# S12_Clocks.net
KiCad netlist of a schematic drawn in Altium Designer
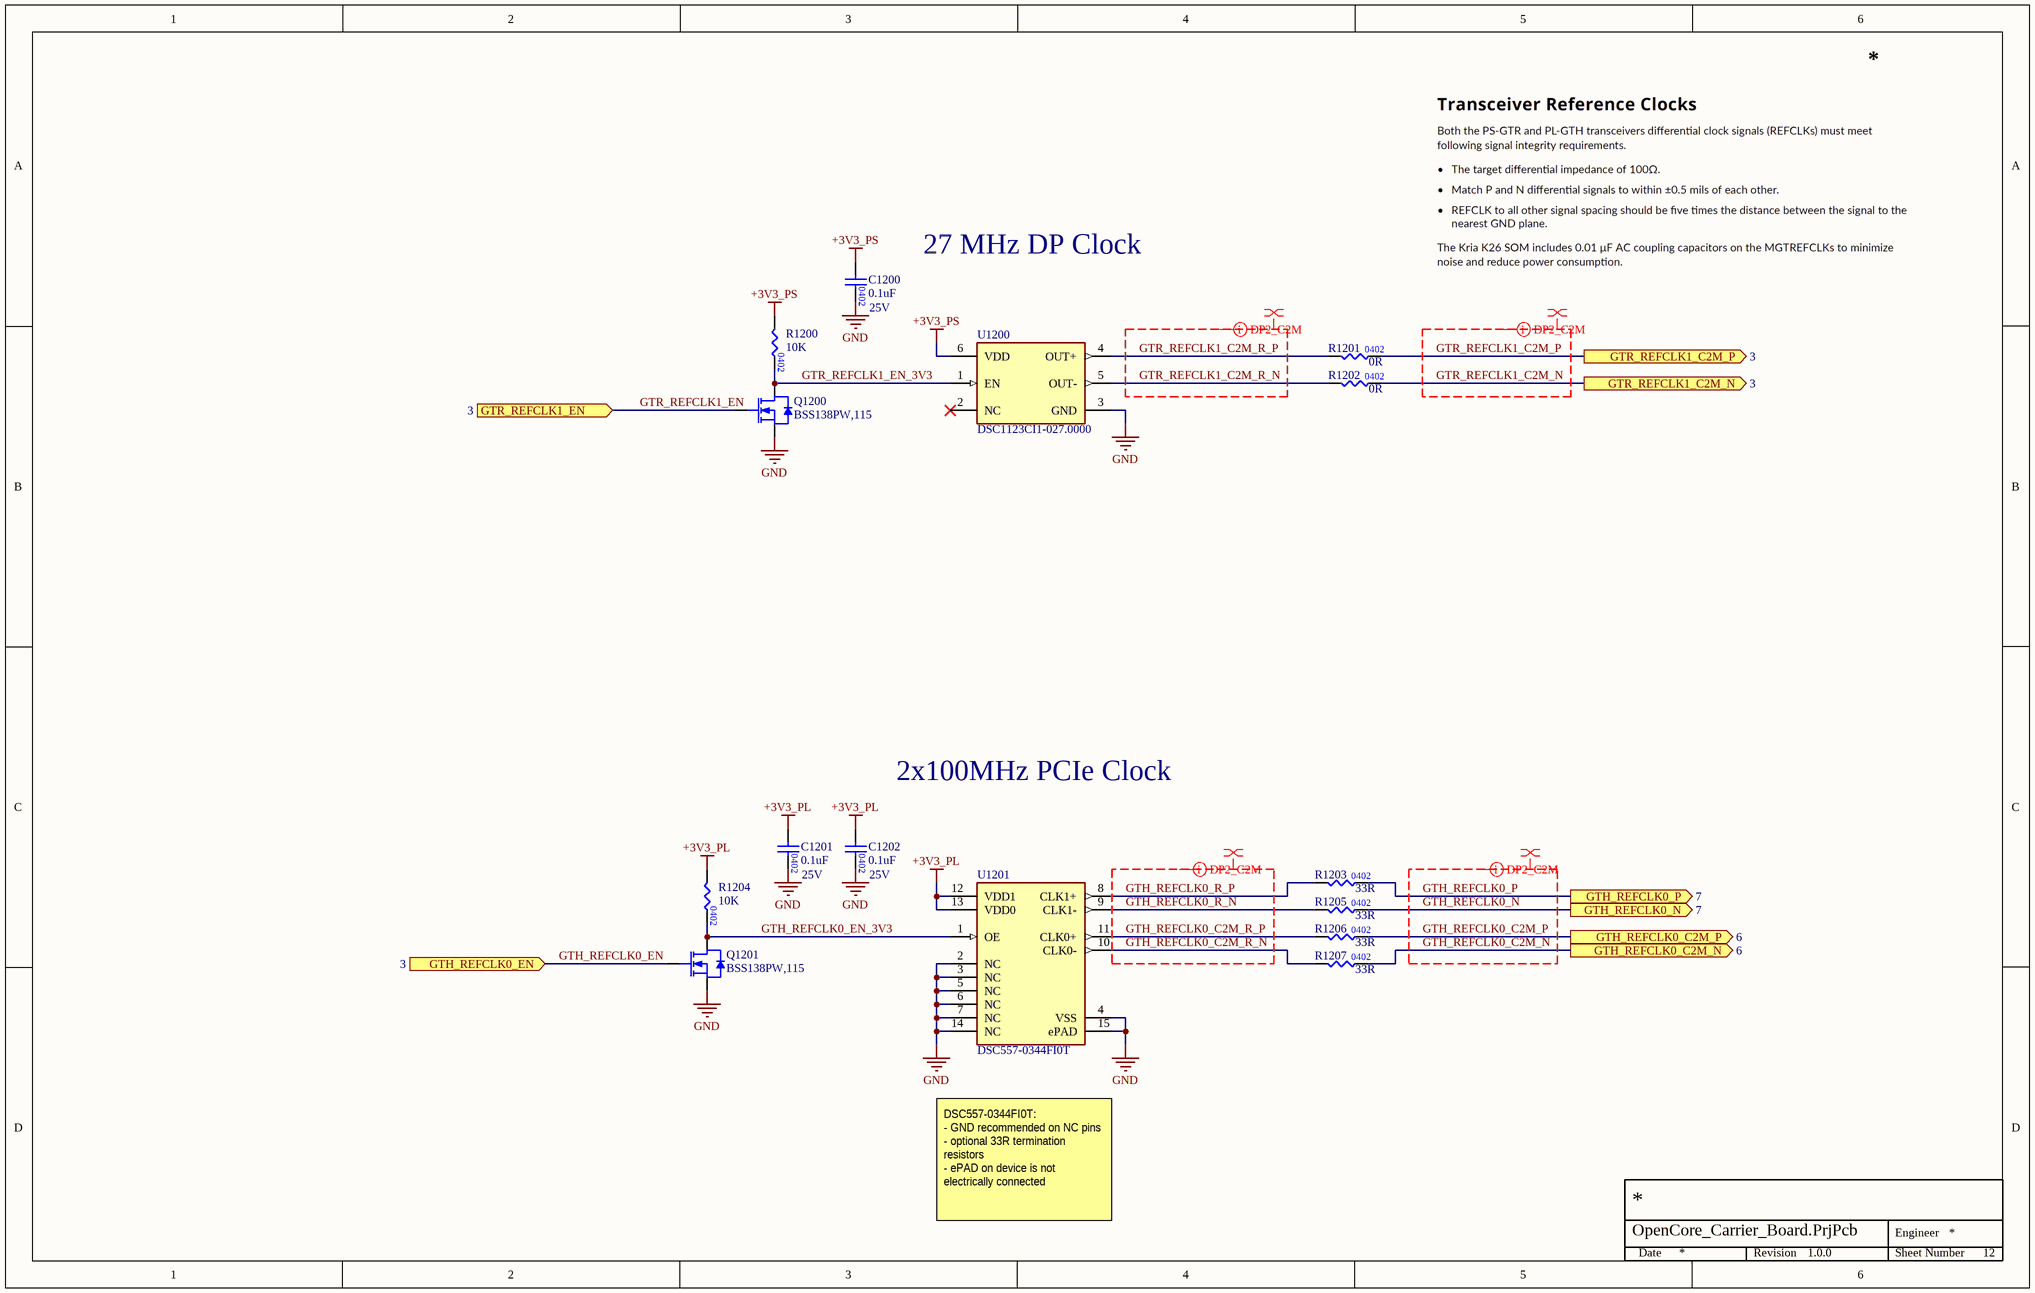
[diagram p0: S12_Clocks.SchDoc]

(export (version "E")
  (design (tool "Eeschema 10.0.6"))
  (components
    (comp (ref "C1200")
      (value "0.1uF")
      (footprint "CAP0402")
      (description "CAP CER 0.1UF 25V X5R 0402")
      (fields
        (field (name "MANUFACTURER") "Samsung Electro-Mechanics")
        (field (name "TOLERANCE") "10%")
        (field (name "VOLTAGE RATING") "25V")
      )
      (libsource (lib "OpenCore_Sch_Lib") (part "CAP_CL05A104KA5NNNC"))
    )
    (comp (ref "C1201")
      (value "0.1uF")
      (footprint "CAP0402")
      (description "CAP CER 0.1UF 25V X5R 0402")
      (fields
        (field (name "MANUFACTURER") "Samsung Electro-Mechanics")
        (field (name "TOLERANCE") "10%")
        (field (name "VOLTAGE RATING") "25V")
      )
      (libsource (lib "OpenCore_Sch_Lib") (part "CAP_CL05A104KA5NNNC"))
    )
    (comp (ref "C1202")
      (value "0.1uF")
      (footprint "CAP0402")
      (description "CAP CER 0.1UF 25V X5R 0402")
      (fields
        (field (name "MANUFACTURER") "Samsung Electro-Mechanics")
        (field (name "TOLERANCE") "10%")
        (field (name "VOLTAGE RATING") "25V")
      )
      (libsource (lib "OpenCore_Sch_Lib") (part "CAP_CL05A104KA5NNNC"))
    )
    (comp (ref "Q1200")
      (value "BSS138PW,115")
      (footprint "NEXPERIA_SOT323")
      (description "MOSFET N-CH 60V 320MA SOT323")
      (libsource (lib "OpenCore_Sch_Lib") (part "BSS138PW,115"))
    )
    (comp (ref "Q1201")
      (value "BSS138PW,115")
      (footprint "NEXPERIA_SOT323")
      (description "MOSFET N-CH 60V 320MA SOT323")
      (libsource (lib "OpenCore_Sch_Lib") (part "BSS138PW,115"))
    )
    (comp (ref "R1200")
      (value "RES_0402")
      (footprint "RES0402")
      (description "RES 10K OHM 1% 1/16W 0402")
      (fields
        (field (name "MANUFACTURER") "YAGEO")
        (field (name "MANUFACTURER PART NUMBER") "RC0402FR-0710KL")
        (field (name "RESISTANCE") "10K")
      )
      (libsource (lib "OpenCore_Sch_Lib") (part ".RES_RC0402FR-0710KL"))
    )
    (comp (ref "R1201")
      (value "RES_0402")
      (footprint "RES0402")
      (description "RES 0 OHM JUMPER 1/16W 0402")
      (fields
        (field (name "MANUFACTURER") "YAGEO")
        (field (name "MANUFACTURER PART NUMBER") "RC0402JR-070RL")
        (field (name "RESISTANCE") "0R")
      )
      (libsource (lib "OpenCore_Sch_Lib") (part ".RES_RC0402JR-070RL"))
    )
    (comp (ref "R1202")
      (value "RES_0402")
      (footprint "RES0402")
      (description "RES 0 OHM JUMPER 1/16W 0402")
      (fields
        (field (name "MANUFACTURER") "YAGEO")
        (field (name "MANUFACTURER PART NUMBER") "RC0402JR-070RL")
        (field (name "RESISTANCE") "0R")
      )
      (libsource (lib "OpenCore_Sch_Lib") (part ".RES_RC0402JR-070RL"))
    )
    (comp (ref "R1203")
      (value "RES_0402")
      (footprint "RES0402")
      (description "RES 33 OHM 1% 1/16W 0402")
      (fields
        (field (name "MANUFACTURER") "YAGEO")
        (field (name "MANUFACTURER PART NUMBER") "RC0402FR-0733RL")
        (field (name "RESISTANCE") "33R")
      )
      (libsource (lib "OpenCore_Sch_Lib") (part ".RES_RC0402FR-0733RL"))
    )
    (comp (ref "R1204")
      (value "RES_0402")
      (footprint "RES0402")
      (description "RES 10K OHM 1% 1/16W 0402")
      (fields
        (field (name "MANUFACTURER") "YAGEO")
        (field (name "MANUFACTURER PART NUMBER") "RC0402FR-0710KL")
        (field (name "RESISTANCE") "10K")
      )
      (libsource (lib "OpenCore_Sch_Lib") (part ".RES_RC0402FR-0710KL"))
    )
    (comp (ref "R1205")
      (value "RES_0402")
      (footprint "RES0402")
      (description "RES 33 OHM 1% 1/16W 0402")
      (fields
        (field (name "MANUFACTURER") "YAGEO")
        (field (name "MANUFACTURER PART NUMBER") "RC0402FR-0733RL")
        (field (name "RESISTANCE") "33R")
      )
      (libsource (lib "OpenCore_Sch_Lib") (part ".RES_RC0402FR-0733RL"))
    )
    (comp (ref "R1206")
      (value "RES_0402")
      (footprint "RES0402")
      (description "RES 33 OHM 1% 1/16W 0402")
      (fields
        (field (name "MANUFACTURER") "YAGEO")
        (field (name "MANUFACTURER PART NUMBER") "RC0402FR-0733RL")
        (field (name "RESISTANCE") "33R")
      )
      (libsource (lib "OpenCore_Sch_Lib") (part ".RES_RC0402FR-0733RL"))
    )
    (comp (ref "R1207")
      (value "RES_0402")
      (footprint "RES0402")
      (description "RES 33 OHM 1% 1/16W 0402")
      (fields
        (field (name "MANUFACTURER") "YAGEO")
        (field (name "MANUFACTURER PART NUMBER") "RC0402FR-0733RL")
        (field (name "RESISTANCE") "33R")
      )
      (libsource (lib "OpenCore_Sch_Lib") (part ".RES_RC0402FR-0733RL"))
    )
    (comp (ref "U1200")
      (value "DSC1123CI1-027.0000")
      (footprint "MICROCHIP_VDFN-6_H5A")
      (description "MEMS OSC XO 27.0000MHZ LVDS SMD")
      (libsource (lib "OpenCore_Sch_Lib") (part "DSC1123CI1-027.0000"))
    )
    (comp (ref "U1201")
      (value "DSC557-0344FI0T")
      (footprint "MICROCHIP_QFN2532-14")
      (description "IC CLOCK GEN PCIE 14QFN")
      (libsource (lib "OpenCore_Sch_Lib") (part "DSC557-0344FI0T"))
    )
  )
  (nets
    (net (code "1") (name "+3V3_PL") (class "Default")
      (node (ref "C1201") (pin "1") (pinfunction "1_1") (pintype "passive"))
      (node (ref "C1202") (pin "1") (pinfunction "1_1") (pintype "passive"))
      (node (ref "R1204") (pin "1") (pinfunction "1_1") (pintype "passive"))
      (node (ref "U1201") (pin "12") (pinfunction "VDD1_12") (pintype "power_in"))
      (node (ref "U1201") (pin "13") (pinfunction "VDD0_13") (pintype "power_in"))
    )
    (net (code "2") (name "+3V3_PS") (class "Default")
      (node (ref "C1200") (pin "1") (pinfunction "1_1") (pintype "passive"))
      (node (ref "R1200") (pin "1") (pinfunction "1_1") (pintype "passive"))
      (node (ref "U1200") (pin "6") (pinfunction "VDD_6") (pintype "power_in"))
    )
    (net (code "3") (name "/GTH_REFCLK0_C2M_N") (class "Default")
      (node (ref "R1207") (pin "2") (pinfunction "2_2") (pintype "passive"))
    )
    (net (code "4") (name "/GTH_REFCLK0_C2M_P") (class "Default")
      (node (ref "R1206") (pin "2") (pinfunction "2_2") (pintype "passive"))
    )
    (net (code "5") (name "/GTH_REFCLK0_C2M_R_N") (class "Default")
      (node (ref "R1207") (pin "1") (pinfunction "1_1") (pintype "passive"))
      (node (ref "U1201") (pin "10") (pinfunction "CLK0-_10") (pintype "output"))
    )
    (net (code "6") (name "/GTH_REFCLK0_C2M_R_P") (class "Default")
      (node (ref "R1206") (pin "1") (pinfunction "1_1") (pintype "passive"))
      (node (ref "U1201") (pin "11") (pinfunction "CLK0+_11") (pintype "output"))
    )
    (net (code "7") (name "/GTH_REFCLK0_EN") (class "Default")
      (node (ref "Q1201") (pin "1") (pinfunction "Gate_1") (pintype "passive"))
    )
    (net (code "8") (name "/GTH_REFCLK0_EN_3V3") (class "Default")
      (node (ref "Q1201") (pin "3") (pinfunction "Drain_3") (pintype "passive"))
      (node (ref "R1204") (pin "2") (pinfunction "2_2") (pintype "passive"))
      (node (ref "U1201") (pin "1") (pinfunction "OE_1") (pintype "input"))
    )
    (net (code "9") (name "/GTH_REFCLK0_N") (class "Default")
      (node (ref "R1205") (pin "2") (pinfunction "2_2") (pintype "passive"))
    )
    (net (code "10") (name "/GTH_REFCLK0_P") (class "Default")
      (node (ref "R1203") (pin "2") (pinfunction "2_2") (pintype "passive"))
    )
    (net (code "11") (name "/GTH_REFCLK0_R_N") (class "Default")
      (node (ref "R1205") (pin "1") (pinfunction "1_1") (pintype "passive"))
      (node (ref "U1201") (pin "9") (pinfunction "CLK1-_9") (pintype "output"))
    )
    (net (code "12") (name "/GTH_REFCLK0_R_P") (class "Default")
      (node (ref "R1203") (pin "1") (pinfunction "1_1") (pintype "passive"))
      (node (ref "U1201") (pin "8") (pinfunction "CLK1+_8") (pintype "output"))
    )
    (net (code "13") (name "/GTR_REFCLK1_C2M_N") (class "Default")
      (node (ref "R1202") (pin "2") (pinfunction "2_2") (pintype "passive"))
    )
    (net (code "14") (name "/GTR_REFCLK1_C2M_P") (class "Default")
      (node (ref "R1201") (pin "2") (pinfunction "2_2") (pintype "passive"))
    )
    (net (code "15") (name "/GTR_REFCLK1_C2M_R_N") (class "Default")
      (node (ref "R1202") (pin "1") (pinfunction "1_1") (pintype "passive"))
      (node (ref "U1200") (pin "5") (pinfunction "OUT-_5") (pintype "output"))
    )
    (net (code "16") (name "/GTR_REFCLK1_C2M_R_P") (class "Default")
      (node (ref "R1201") (pin "1") (pinfunction "1_1") (pintype "passive"))
      (node (ref "U1200") (pin "4") (pinfunction "OUT+_4") (pintype "output"))
    )
    (net (code "17") (name "/GTR_REFCLK1_EN") (class "Default")
      (node (ref "Q1200") (pin "1") (pinfunction "Gate_1") (pintype "passive"))
    )
    (net (code "18") (name "/GTR_REFCLK1_EN_3V3") (class "Default")
      (node (ref "Q1200") (pin "3") (pinfunction "Drain_3") (pintype "passive"))
      (node (ref "R1200") (pin "2") (pinfunction "2_2") (pintype "passive"))
      (node (ref "U1200") (pin "1") (pinfunction "EN_1") (pintype "input"))
    )
    (net (code "19") (name "GND") (class "Default")
      (node (ref "C1200") (pin "2") (pinfunction "2_2") (pintype "passive"))
      (node (ref "C1201") (pin "2") (pinfunction "2_2") (pintype "passive"))
      (node (ref "C1202") (pin "2") (pinfunction "2_2") (pintype "passive"))
      (node (ref "Q1200") (pin "2") (pinfunction "Source_2") (pintype "passive"))
      (node (ref "Q1201") (pin "2") (pinfunction "Source_2") (pintype "passive"))
      (node (ref "U1200") (pin "3") (pinfunction "GND_3") (pintype "power_in"))
      (node (ref "U1201") (pin "14") (pinfunction "NC_14") (pintype "passive"))
      (node (ref "U1201") (pin "15") (pinfunction "ePAD_15") (pintype "power_in"))
      (node (ref "U1201") (pin "2") (pinfunction "NC_2") (pintype "passive"))
      (node (ref "U1201") (pin "3") (pinfunction "NC_3") (pintype "passive"))
      (node (ref "U1201") (pin "4") (pinfunction "VSS_4") (pintype "power_in"))
      (node (ref "U1201") (pin "5") (pinfunction "NC_5") (pintype "passive"))
      (node (ref "U1201") (pin "6") (pinfunction "NC_6") (pintype "passive"))
      (node (ref "U1201") (pin "7") (pinfunction "NC_7") (pintype "passive"))
    )
    (net (code "20") (name "unconnected-(U1200-NC-Pad2)") (class "Default")
      (node (ref "U1200") (pin "2") (pinfunction "NC_2") (pintype "passive+no_connect"))
    )
  )
)
